# PX4FLOW2_0_Sensors_CAN_X0.net
KiCad netlist of a schematic drawn in Altium Designer
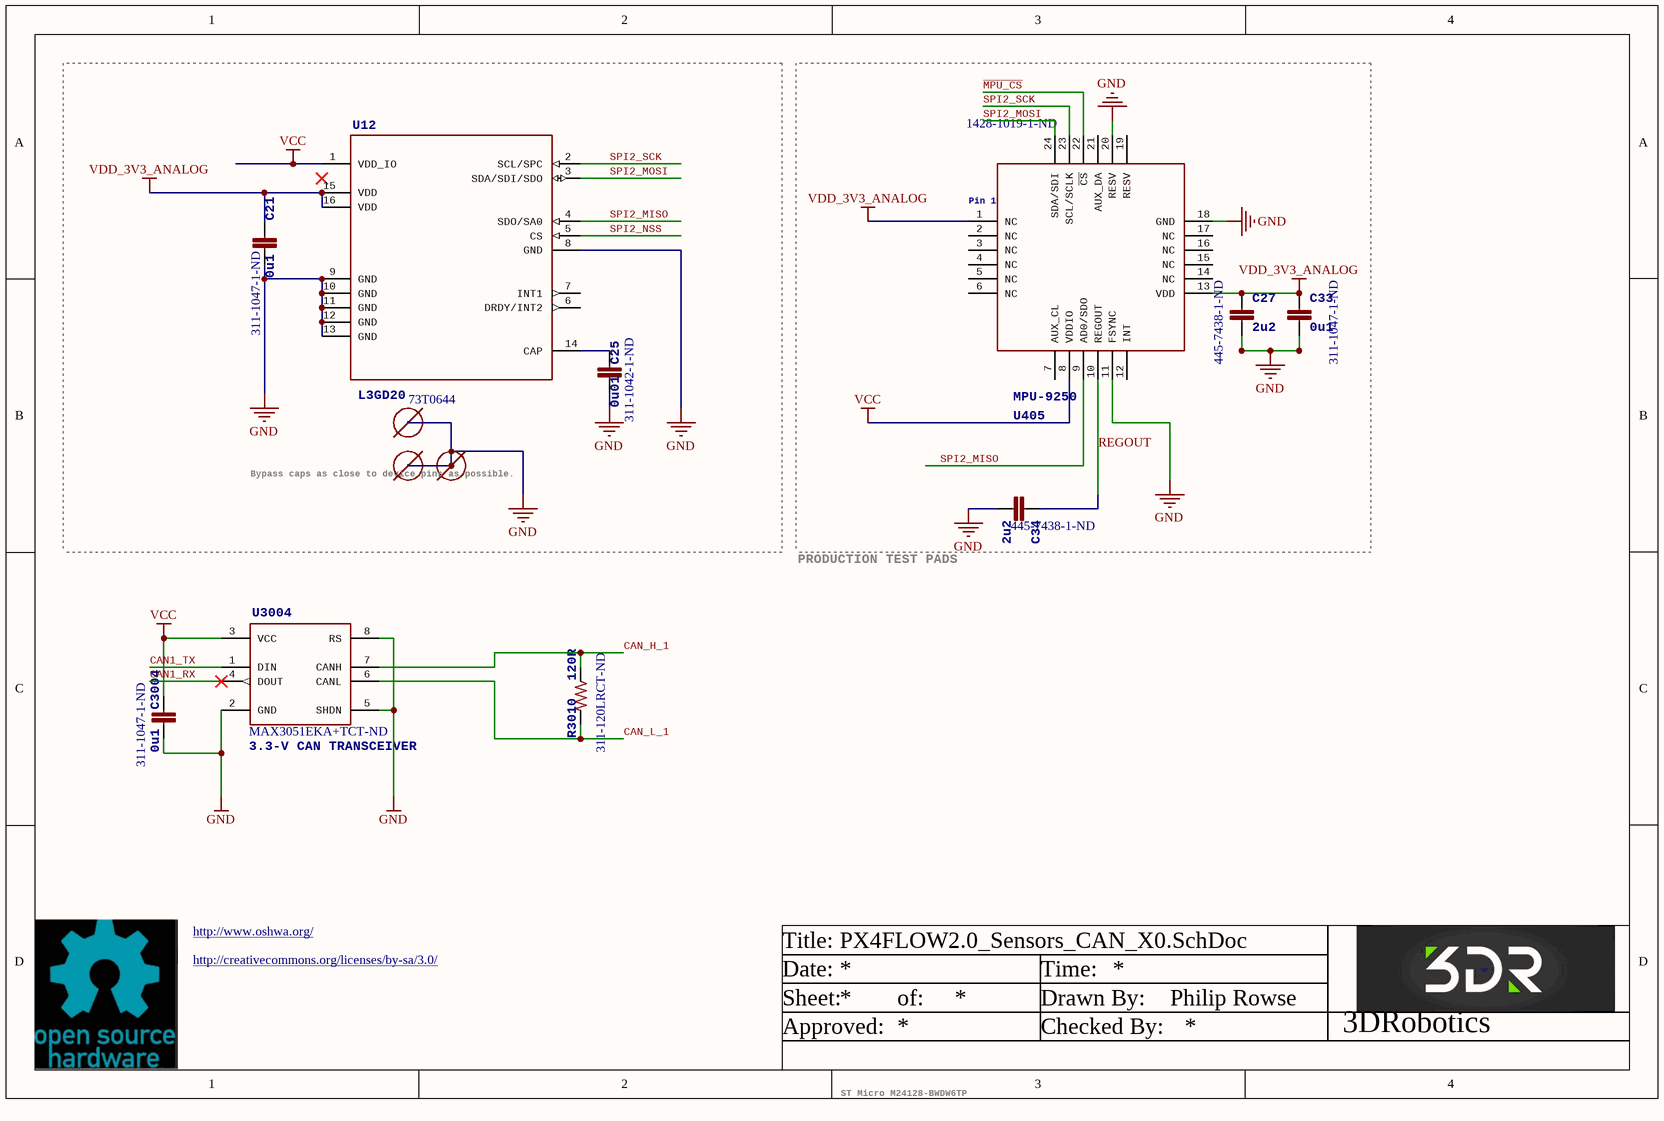
[diagram p0: PX4FLOW2.0_Sensors_CAN_X0.SchDoc]

(export (version "E")
  (design (tool "Eeschema 10.0.6"))
  (components
    (comp (ref "C21")
      (value "0u1")
      (footprint "0402-CAP")
      (description "CapacitorStandard 0603 ceramic capacitor, and 0.1\" leaded capacitor.")
      (fields
        (field (name "PARTNO") "CC0402ZRY5V7BB104")
        (field (name "SUPPLIER PART NUMBER 1") "311-1047-1-ND")
      )
      (libsource (lib "pixhawk2") (part "CAP0402-CAP"))
    )
    (comp (ref "C25")
      (value "0u01")
      (footprint "0402-CAP")
      (description "CapacitorStandard 0603 ceramic capacitor, and 0.1\" leaded capacitor.")
      (fields
        (field (name "PARTNO") "CC0402KRX7R7BB103")
        (field (name "SUPPLIER PART NUMBER 1") "311-1042-1-ND")
      )
      (libsource (lib "pixhawk2") (part "CAP0402-CAP"))
    )
    (comp (ref "C27")
      (value "2u2")
      (footprint "0603-CAP")
      (description "Capacitor, 2.2uF, 16V, 10%, X6S, 0603, Ceramic")
      (fields
        (field (name "PARTNO") "C1608X6S1C225K080AC")
        (field (name "SUPPLIER PART NUMBER 1") "445-7438-1-ND")
        (field (name "3DR_PARTNO") "ECM0619")
      )
      (libsource (lib "") (part "CAPACITOR-0603_1"))
    )
    (comp (ref "C33")
      (value "0u1")
      (footprint "0402-CAP")
      (description "Capacitor, 0.1uF, 16V, Y5V, 0402, Ceramic")
      (fields
        (field (name "PARTNO") "CC0402ZRY5V7BB104")
        (field (name "SUPPLIER PART NUMBER 1") "311-1047-1-ND")
        (field (name "3DR_PARTNO") "ECM0700")
      )
      (libsource (lib "lib_pixhawk") (part "CAPACITOR-0402"))
    )
    (comp (ref "C34")
      (value "2u2")
      (footprint "0603-CAP")
      (description "Capacitor, 2.2uF, 16V, 10%, X6S, 0603, Ceramic")
      (fields
        (field (name "PARTNO") "C1608X6S1C225K080AC")
        (field (name "SUPPLIER PART NUMBER 1") "445-7438-1-ND")
        (field (name "3DR_PARTNO") "ECM0619")
      )
      (libsource (lib "lib_pixhawk") (part "CAPACITOR-0603"))
    )
    (comp (ref "C3004")
      (value "0u1")
      (footprint "0402-CAP")
      (description "CAP CER 0.1UF 16V Y5V 0402")
      (fields
        (field (name "PARTNO") "CC0402ZRY5V7BB104")
        (field (name "SUPPLIER PART NUMBER 1") "311-1047-1-ND")
        (field (name "3DR_PARTNO") "ECM0700")
      )
      (libsource (lib "pixhawk2") (part "CAP0402"))
    )
    (comp (ref "R3010")
      (value "120R")
      (footprint "R0402")
      (description "RES 120 OHM 1/16W 1% 0402 SMD")
      (fields
        (field (name "PARTNO") "RC0402FR-07120RL")
        (field (name "SUPPLIER PART NUMBER 1") "311-120LRCT-ND")
        (field (name "3DR_PARTNO") "ECM0820")
      )
      (libsource (lib "pixhawk2") (part "RESISTOR0402-RES"))
    )
    (comp (ref "U$1")
      (value "MOUNT-HOLE3.1MM")
      (footprint "MOUNT-HOLE3.1")
      (libsource (lib "pixhawk2") (part "MOUNT-HOLE3.1MM"))
    )
    (comp (ref "U$3")
      (value "MOUNT-HOLE3.1MM")
      (footprint "MOUNT-HOLE3.1")
      (libsource (lib "pixhawk2") (part "MOUNT-HOLE3.1MM"))
    )
    (comp (ref "U$4")
      (value "MOUNT-HOLE3.1MM")
      (footprint "MOUNT-HOLE3.1")
      (libsource (lib "pixhawk2") (part "MOUNT-HOLE3.1MM"))
    )
    (comp (ref "U12")
      (value "L3GD20")
      (footprint "L3GD20")
      (description "Sensor, Low-power, Three-axis, Angular rate")
      (fields (field (name "SUPPLIER PART NUMBER 1") "73T0644") (field (name "3DR_PARTNO") "ECM0827"))
      (libsource (lib "pixhawk2") (part "L3GD20"))
    )
    (comp (ref "U405")
      (value "MPU-9250")
      (footprint "MPU-6500")
      (fields (field (name "PIN 1") "Pin 1") (field (name "SUPPLIER PART NUMBER 1") "1428-1019-1-ND"))
      (libsource (lib "pixhawk2") (part "MPU-6500"))
    )
    (comp (ref "U3004")
      (value "3.3-V CAN TRANSCEIVER")
      (footprint "SOT23-8")
      (description "IC TXRX CAN 1MBPS SOT23-8")
      (fields
        (field (name "SUPPLIER PART NUMBER 1") "MAX3051EKA+TCT-ND")
        (field (name "3DR_PARTNO") "ECM0831")
        (field (name "PARTNO") "MAX3051EKA+T")
      )
      (libsource (lib "pixhawk2") (part "MAX3051MAX3051EKA"))
    )
  )
  (nets
    (net (code "1") (name "/CAN1_RX") (class "Default")
      (node (ref "U3004") (pin "4") (pinfunction "DOUT_4") (pintype "output+no_connect"))
    )
    (net (code "2") (name "/CAN1_TX") (class "Default")
      (node (ref "U3004") (pin "1") (pinfunction "DIN_1") (pintype "passive"))
    )
    (net (code "3") (name "/CAN_H_1") (class "Default")
      (node (ref "R3010") (pin "1") (pinfunction "1_1") (pintype "passive"))
      (node (ref "U3004") (pin "7") (pinfunction "CANH_7") (pintype "passive"))
    )
    (net (code "4") (name "/CAN_L_1") (class "Default")
      (node (ref "R3010") (pin "2") (pinfunction "2_2") (pintype "passive"))
      (node (ref "U3004") (pin "6") (pinfunction "CANL_6") (pintype "passive"))
    )
    (net (code "5") (name "/REGOUT") (class "Default")
      (node (ref "C34") (pin "P$1") (pinfunction "1_P$1") (pintype "passive"))
      (node (ref "U405") (pin "10") (pinfunction "REGOUT_10") (pintype "passive"))
    )
    (net (code "6") (name "/SPI2_MISO") (class "Default")
      (node (ref "U12") (pin "4") (pinfunction "SDO/SA0_4") (pintype "input"))
      (node (ref "U405") (pin "9") (pinfunction "AD0/SDO_9") (pintype "passive"))
    )
    (net (code "7") (name "/SPI2_MOSI") (class "Default")
      (node (ref "U12") (pin "3") (pinfunction "SDA/SDI/SDO_3") (pintype "bidirectional"))
      (node (ref "U405") (pin "24") (pinfunction "SDA/SDI_24") (pintype "passive"))
    )
    (net (code "8") (name "/SPI2_NSS") (class "Default")
      (node (ref "U12") (pin "5") (pinfunction "CS_5") (pintype "input"))
    )
    (net (code "9") (name "/SPI2_SCK") (class "Default")
      (node (ref "U12") (pin "2") (pinfunction "SCL/SPC_2") (pintype "input"))
      (node (ref "U405") (pin "23") (pinfunction "SCL/SCLK_23") (pintype "passive"))
    )
    (net (code "10") (name "/~{MPU_CS}") (class "Default")
      (node (ref "U405") (pin "22") (pinfunction "~{CS}_22") (pintype "passive"))
    )
    (net (code "11") (name "GND") (class "Default")
      (node (ref "C21") (pin "2") (pinfunction "2_2") (pintype "passive"))
      (node (ref "C25") (pin "2") (pinfunction "2_2") (pintype "passive"))
      (node (ref "C27") (pin "P$2") (pinfunction "2_P$2") (pintype "passive"))
      (node (ref "C3004") (pin "P$2") (pinfunction "2_P$2") (pintype "passive"))
      (node (ref "C33") (pin "P$2") (pinfunction "2_P$2") (pintype "passive"))
      (node (ref "C34") (pin "P$2") (pinfunction "2_P$2") (pintype "passive"))
      (node (ref "U$1") (pin "1") (pinfunction "1_1") (pintype "passive"))
      (node (ref "U$3") (pin "1") (pinfunction "1_1") (pintype "passive"))
      (node (ref "U$4") (pin "1") (pinfunction "1_1") (pintype "passive"))
      (node (ref "U12") (pin "10") (pinfunction "GND_10") (pintype "power_in"))
      (node (ref "U12") (pin "11") (pinfunction "GND_11") (pintype "power_in"))
      (node (ref "U12") (pin "12") (pinfunction "GND_12") (pintype "power_in"))
      (node (ref "U12") (pin "13") (pinfunction "GND_13") (pintype "power_in"))
      (node (ref "U12") (pin "8") (pinfunction "GND_8") (pintype "power_in"))
      (node (ref "U12") (pin "9") (pinfunction "GND_9") (pintype "power_in"))
      (node (ref "U3004") (pin "2") (pinfunction "GND_2") (pintype "power_in"))
      (node (ref "U3004") (pin "5") (pinfunction "SHDN_5") (pintype "passive"))
      (node (ref "U3004") (pin "8") (pinfunction "RS_8") (pintype "passive"))
      (node (ref "U405") (pin "11") (pinfunction "FSYNC_11") (pintype "passive"))
      (node (ref "U405") (pin "18") (pinfunction "GND_18") (pintype "passive"))
      (node (ref "U405") (pin "20") (pinfunction "RESV_20") (pintype "passive"))
    )
    (net (code "12") (name "Net-(U12-CAP)") (class "Default")
      (node (ref "C25") (pin "1") (pinfunction "1_1") (pintype "passive"))
      (node (ref "U12") (pin "14") (pinfunction "CAP_14") (pintype "passive"))
    )
    (net (code "13") (name "VCC") (class "Default")
      (node (ref "C3004") (pin "P$1") (pinfunction "1_P$1") (pintype "passive"))
      (node (ref "U12") (pin "1") (pinfunction "VDD_IO_1") (pintype "power_in"))
      (node (ref "U3004") (pin "3") (pinfunction "VCC_3") (pintype "passive"))
      (node (ref "U405") (pin "8") (pinfunction "VDDIO_8") (pintype "passive"))
    )
    (net (code "14") (name "VDD_3V3_ANALOG") (class "Default")
      (node (ref "C21") (pin "1") (pinfunction "1_1") (pintype "passive"))
      (node (ref "C27") (pin "P$1") (pinfunction "1_P$1") (pintype "passive"))
      (node (ref "C33") (pin "P$1") (pinfunction "1_P$1") (pintype "passive"))
      (node (ref "U12") (pin "15") (pinfunction "VDD_15") (pintype "power_in"))
      (node (ref "U12") (pin "16") (pinfunction "VDD_16") (pintype "power_in"))
      (node (ref "U405") (pin "1") (pinfunction "NC_1") (pintype "passive"))
      (node (ref "U405") (pin "13") (pinfunction "VDD_13") (pintype "passive"))
    )
    (net (code "15") (name "unconnected-(U12-DRDY{slash}INT2-Pad6)") (class "Default")
      (node (ref "U12") (pin "6") (pinfunction "DRDY/INT2_6") (pintype "output"))
    )
    (net (code "16") (name "unconnected-(U12-INT1-Pad7)") (class "Default")
      (node (ref "U12") (pin "7") (pinfunction "INT1_7") (pintype "output"))
    )
    (net (code "17") (name "unconnected-(U405-AUX_CL-Pad7)") (class "Default")
      (node (ref "U405") (pin "7") (pinfunction "AUX_CL_7") (pintype "passive"))
    )
    (net (code "18") (name "unconnected-(U405-AUX_DA-Pad21)") (class "Default")
      (node (ref "U405") (pin "21") (pinfunction "AUX_DA_21") (pintype "passive"))
    )
    (net (code "19") (name "unconnected-(U405-INT-Pad12)") (class "Default")
      (node (ref "U405") (pin "12") (pinfunction "INT_12") (pintype "passive"))
    )
    (net (code "20") (name "unconnected-(U405-NC-Pad2)") (class "Default")
      (node (ref "U405") (pin "2") (pinfunction "NC_2") (pintype "passive"))
    )
    (net (code "21") (name "unconnected-(U405-NC-Pad3)") (class "Default")
      (node (ref "U405") (pin "3") (pinfunction "NC_3") (pintype "passive"))
    )
    (net (code "22") (name "unconnected-(U405-NC-Pad4)") (class "Default")
      (node (ref "U405") (pin "4") (pinfunction "NC_4") (pintype "passive"))
    )
    (net (code "23") (name "unconnected-(U405-NC-Pad5)") (class "Default")
      (node (ref "U405") (pin "5") (pinfunction "NC_5") (pintype "passive"))
    )
    (net (code "24") (name "unconnected-(U405-NC-Pad6)") (class "Default")
      (node (ref "U405") (pin "6") (pinfunction "NC_6") (pintype "passive"))
    )
    (net (code "25") (name "unconnected-(U405-NC-Pad14)") (class "Default")
      (node (ref "U405") (pin "14") (pinfunction "NC_14") (pintype "passive"))
    )
    (net (code "26") (name "unconnected-(U405-NC-Pad15)") (class "Default")
      (node (ref "U405") (pin "15") (pinfunction "NC_15") (pintype "passive"))
    )
    (net (code "27") (name "unconnected-(U405-NC-Pad16)") (class "Default")
      (node (ref "U405") (pin "16") (pinfunction "NC_16") (pintype "passive"))
    )
    (net (code "28") (name "unconnected-(U405-NC-Pad17)") (class "Default")
      (node (ref "U405") (pin "17") (pinfunction "NC_17") (pintype "passive"))
    )
    (net (code "29") (name "unconnected-(U405-RESV-Pad19)") (class "Default")
      (node (ref "U405") (pin "19") (pinfunction "RESV_19") (pintype "passive"))
    )
  )
)
